# HUT_BUI.net
KiCad netlist of a schematic drawn in Altium Designer
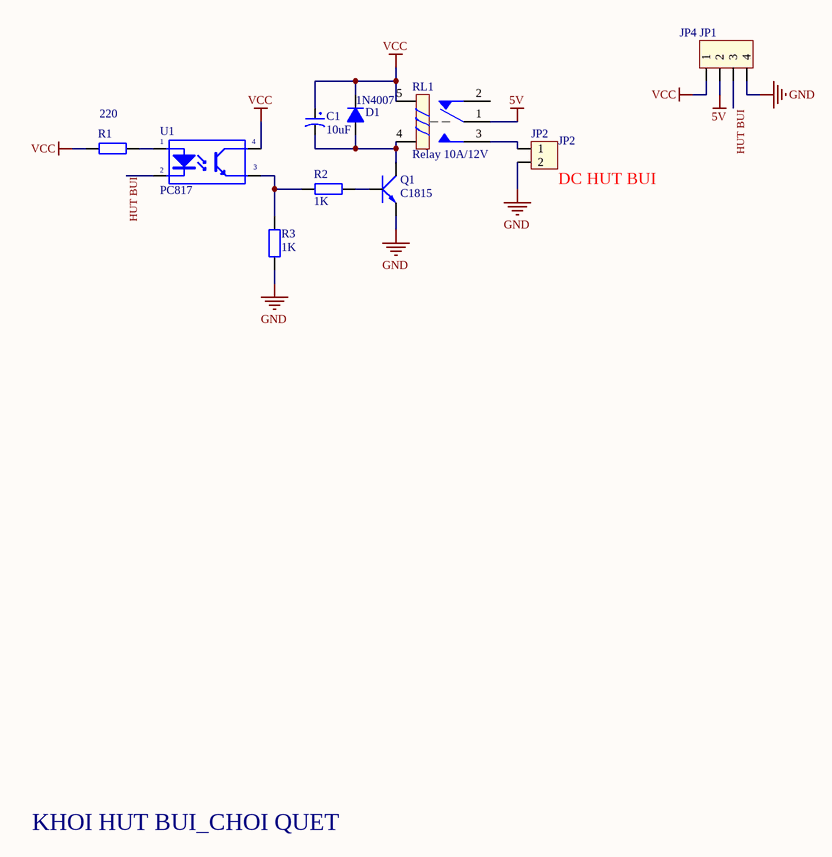
[diagram p0: HUT BUI.SchDoc]

(export (version "E")
  (design (tool "Eeschema 10.0.6"))
  (components
    (comp (ref "C1")
      (value "10uF")
      (footprint "CP1/2")
      (description "Cap P  0,1uF < 22uF , 16 - 50V")
      (libsource (lib "syhaunguyen") (part "CP1"))
    )
    (comp (ref "D1")
      (value "1N4007")
      (footprint "D1A")
      (description "Diode 1A")
      (libsource (lib "syhaunguyen") (part "D1A"))
    )
    (comp (ref "JP1")
      (value "JP4")
      (footprint "CON4")
      (description "Connector 4")
      (libsource (lib "syhaunguyen") (part "Con4"))
    )
    (comp (ref "JP2")
      (value "JP2")
      (footprint "CON2")
      (description "Connector 2")
      (libsource (lib "syhaunguyen") (part "Con2"))
    )
    (comp (ref "Q1")
      (value "C1815")
      (footprint "QTO-92")
      (description "NPN 600mW, ECB")
      (libsource (lib "syhaunguyen") (part "C1815"))
    )
    (comp (ref "R1")
      (value "220")
      (footprint "R1/4W")
      (description "Resistor 1/4W")
      (libsource (lib "syhaunguyen") (part "R1/4W"))
    )
    (comp (ref "R2")
      (value "1K")
      (footprint "R1/4W")
      (description "Resistor 1/4W")
      (libsource (lib "syhaunguyen") (part "R1/4W"))
    )
    (comp (ref "R3")
      (value "1K")
      (footprint "R1/4W")
      (description "Resistor 1/4W")
      (libsource (lib "syhaunguyen") (part "R1/4W"))
    )
    (comp (ref "RL1")
      (value "Relay 10A/12V")
      (footprint "RL_SPDT_10A")
      (description "Relay SPDT,10A - 12VDC 5 Pin")
      (libsource (lib "syhaunguyen") (part "Relay 1"))
    )
    (comp (ref "U1")
      (value "PC817")
      (footprint "DIP4/W0.3")
      (description "Single Opto")
      (libsource (lib "syhaunguyen") (part "PC817"))
    )
  )
  (nets
    (net (code "1") (name "/HUT BUI") (class "Default")
      (node (ref "JP1") (pin "3") (pinfunction "3_3") (pintype "passive"))
      (node (ref "U1") (pin "2") (pinfunction "K_2") (pintype "passive"))
    )
    (net (code "2") (name "5V") (class "Default")
      (node (ref "JP1") (pin "2") (pinfunction "2_2") (pintype "passive"))
      (node (ref "RL1") (pin "1") (pinfunction "1_1") (pintype "passive"))
    )
    (net (code "3") (name "GND") (class "Default")
      (node (ref "JP1") (pin "4") (pinfunction "4_4") (pintype "passive"))
      (node (ref "JP2") (pin "2") (pinfunction "2_2") (pintype "passive"))
      (node (ref "Q1") (pin "1") (pinfunction "E_1") (pintype "passive"))
      (node (ref "R3") (pin "1") (pinfunction "1_1") (pintype "passive"))
    )
    (net (code "4") (name "Net-(D1-A)") (class "Default")
      (node (ref "C1") (pin "2") (pinfunction "2_2") (pintype "passive"))
      (node (ref "D1") (pin "1") (pinfunction "A_1") (pintype "passive"))
      (node (ref "Q1") (pin "2") (pinfunction "C_2") (pintype "passive"))
      (node (ref "RL1") (pin "4") (pinfunction "4_4") (pintype "passive"))
    )
    (net (code "5") (name "Net-(JP2-Pad1)") (class "Default")
      (node (ref "JP2") (pin "1") (pinfunction "1_1") (pintype "passive"))
      (node (ref "RL1") (pin "3") (pinfunction "3_3") (pintype "passive"))
    )
    (net (code "6") (name "Net-(Q1-B)") (class "Default")
      (node (ref "Q1") (pin "3") (pinfunction "B_3") (pintype "passive"))
      (node (ref "R2") (pin "1") (pinfunction "1_1") (pintype "passive"))
    )
    (net (code "7") (name "Net-(U1-A)") (class "Default")
      (node (ref "R1") (pin "2") (pinfunction "2_2") (pintype "passive"))
      (node (ref "U1") (pin "1") (pinfunction "A_1") (pintype "passive"))
    )
    (net (code "8") (name "Net-(U1-E)") (class "Default")
      (node (ref "R2") (pin "2") (pinfunction "2_2") (pintype "passive"))
      (node (ref "R3") (pin "2") (pinfunction "2_2") (pintype "passive"))
      (node (ref "U1") (pin "3") (pinfunction "E_3") (pintype "passive"))
    )
    (net (code "9") (name "VCC") (class "Default")
      (node (ref "C1") (pin "1") (pinfunction "1_1") (pintype "passive"))
      (node (ref "D1") (pin "2") (pinfunction "K_2") (pintype "passive"))
      (node (ref "JP1") (pin "1") (pinfunction "1_1") (pintype "passive"))
      (node (ref "R1") (pin "1") (pinfunction "1_1") (pintype "passive"))
      (node (ref "RL1") (pin "5") (pinfunction "5_5") (pintype "passive"))
      (node (ref "U1") (pin "4") (pinfunction "C_4") (pintype "passive"))
    )
    (net (code "10") (name "unconnected-(RL1-Pad2)") (class "Default")
      (node (ref "RL1") (pin "2") (pinfunction "2_2") (pintype "passive"))
    )
  )
)
